# PAPAYA_PCB.net
KiCad netlist of a schematic drawn in Altium Designer
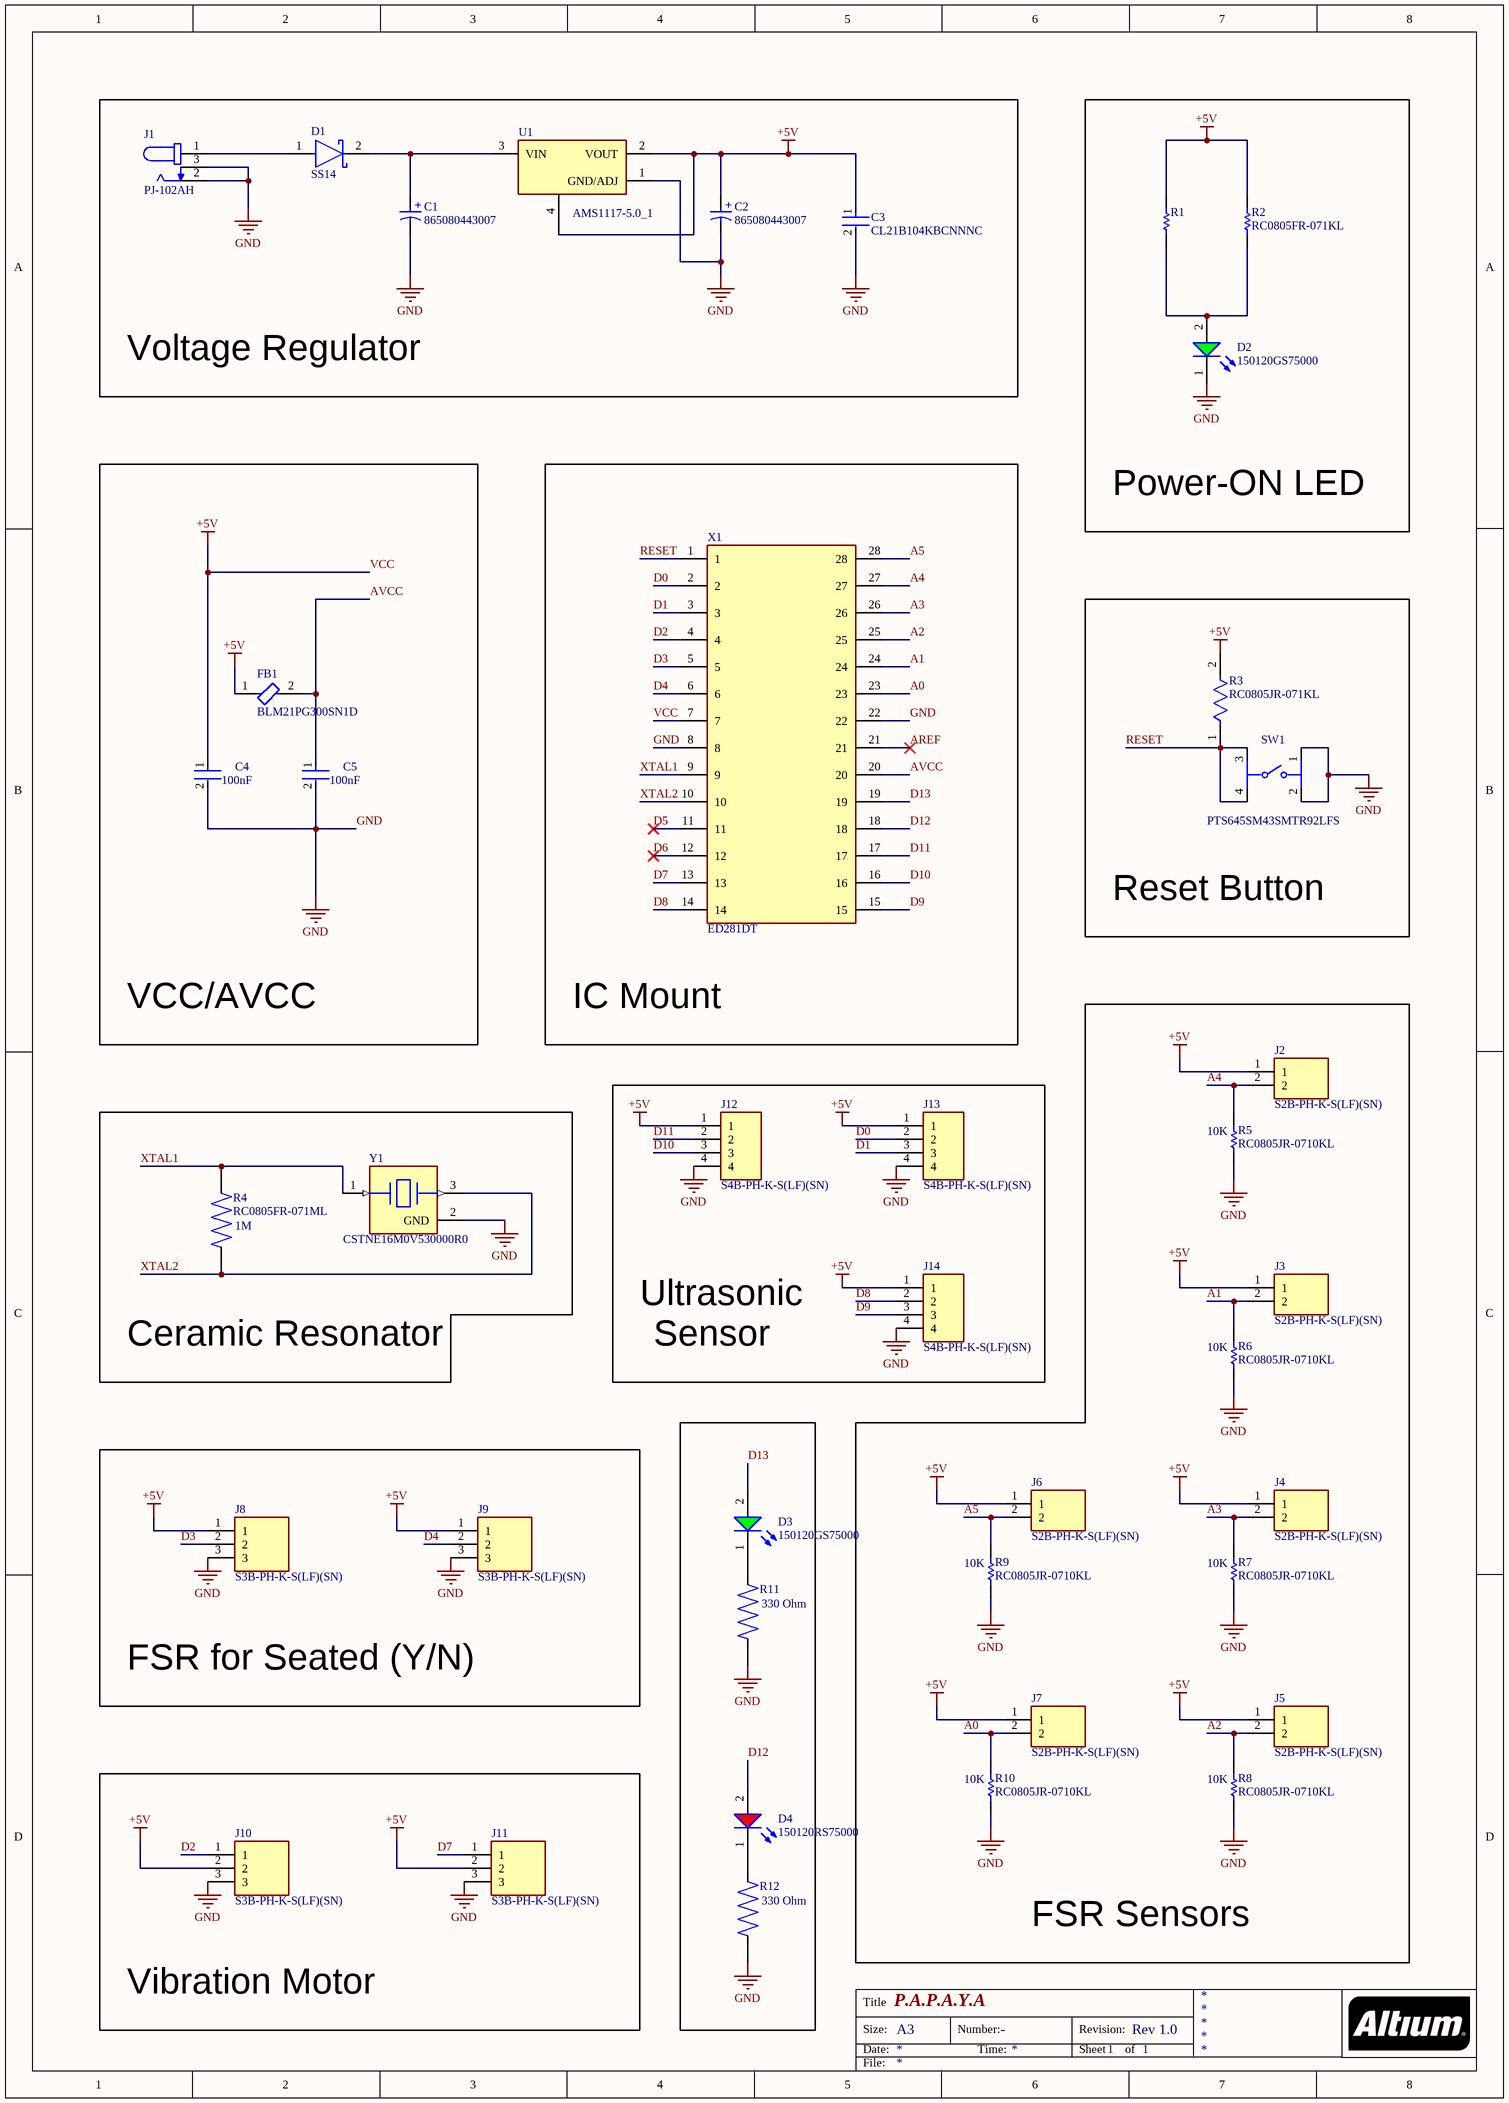
[diagram p0: PAPAYA_PCB.SchDoc]

(export (version "E")
  (design (tool "Eeschema 10.0.6"))
  (components
    (comp (ref "C1")
      (value "865080443007")
      (footprint "WCAP-ASLI_D6.3H5.5")
      (description "865080443007 WCAP-ASLI Aluminum Electrolytic Capacitors")
      (fields (field (name "TOLERANCE") "20%"))
      (libsource (lib "Altium Content Vault") (part "Capacitor_Polarized"))
    )
    (comp (ref "C2")
      (value "865080443007")
      (footprint "WCAP-ASLI_D6.3H5.5")
      (description "865080443007 WCAP-ASLI Aluminum Electrolytic Capacitors")
      (fields (field (name "TOLERANCE") "20%"))
      (libsource (lib "Altium Content Vault") (part "Capacitor_Polarized"))
    )
    (comp (ref "C3")
      (value "CL21B104KBCNNNC")
      (footprint "FP-CL21-IPC_C")
      (description "CL21 Series 0805 100nF 50V ±10% Tolerance X7R Multilayer Ceramic Chip Capacitor")
      (fields (field (name "TOLERANCE") "10%") (field (name "VOLTAGE") "50V"))
      (libsource (lib "Altium Content Vault") (part "b4654b650e69147ec39a6b967a45e02"))
    )
    (comp (ref "C4")
      (value "CL21B104KBCNNNC")
      (footprint "FP-CL21-IPC_C")
      (description "CL21 Series 0805 100nF 50V ±10% Tolerance X7R Multilayer Ceramic Chip Capacitor")
      (fields
        (field (name "TOLERANCE") "10%")
        (field (name "CAPACITANCE") "100nF")
        (field (name "VOLTAGE") "50V")
      )
      (libsource (lib "Altium Content Vault") (part "b4654b650e69147ec39a6b967a45e02"))
    )
    (comp (ref "C5")
      (value "CL21B104KBCNNNC")
      (footprint "FP-CL21-IPC_C")
      (description "CL21 Series 0805 100nF 50V ±10% Tolerance X7R Multilayer Ceramic Chip Capacitor")
      (fields
        (field (name "TOLERANCE") "10%")
        (field (name "CAPACITANCE") "100nF")
        (field (name "VOLTAGE") "50V")
      )
      (libsource (lib "Altium Content Vault") (part "b4654b650e69147ec39a6b967a45e02"))
    )
    (comp (ref "D1")
      (value "SS14")
      (footprint "FP-403AE-MFG")
      (description "DIODE SCHOTTKY 40V 1A SMA")
      (fields
        (field (name "MANUFACTURER") "ON Semiconductor")
        (field (name "OCTOPART") "https://octopart.com/ss14-on+semiconductor-29205033")
      )
      (libsource (lib "Altium Content Vault") (part "360ad2f4ac25a952324d13796385471"))
    )
    (comp (ref "D2")
      (value "150120GS75000")
      (footprint "WL-SMCW_1206_150120xx75000")
      (description "WURTH ELEKTRONIK - 150080GS75000 - LED, Green, SMD, 0805, 30 mA, 3.2 V, 520 nm")
      (libsource (lib "Altium Content Vault") (part "LED_Green_2A-1K"))
    )
    (comp (ref "D3")
      (value "150120GS75000")
      (footprint "WL-SMCW_1206_150120xx75000")
      (description "WURTH ELEKTRONIK - 150080GS75000 - LED, Green, SMD, 0805, 30 mA, 3.2 V, 520 nm")
      (libsource (lib "Altium Content Vault") (part "LED_Green_2A-1K"))
    )
    (comp (ref "D4")
      (value "150120RS75000")
      (footprint "WL-SMCW_1206_150120xx75000")
      (description "LED Uni-Color Red 630nm 2-Pin Chip 0805(2012Metric) T/R")
      (libsource (lib "Altium Content Vault") (part "LED_Red_2A-1K"))
    )
    (comp (ref "FB1")
      (value "BLM21PG300SN1D")
      (footprint "FP-BLM21-0_2-t0_85-e0_5-d-MFG")
      (description "Chip Ferrite Bead, 0805, 30Ω @ 100MHz, 0.014Ω, , 4A")
      (fields (field (name "TOLERANCE") "25%"))
      (libsource (lib "Altium Content Vault") (part "5f30dd21d616792df468990f7003faa"))
    )
    (comp (ref "J1")
      (value "PJ-102AH")
      (footprint "CUI_PJ-102AH")
      (description "2.0 x 6.5 mm, 5.0 A, Horizontal, Through Hole, Tapered Pins, Dc Power Jack Connector")
      (fields (field (name "MF") "Same Sky"))
      (libsource (lib "Schlib1") (part "PJ-102AH"))
    )
    (comp (ref "J2")
      (value "S2B-PH-K-S(LF)(SN)")
      (footprint "JST_S2B-PH-K-S(LF)(SN)")
      (description "Connector Header Through Hole, Right Angle 2 position")
      (fields (field (name "MF") "JST Sales America Inc."))
      (libsource (lib "Schlib1") (part "S2B-PH-K-S(LF)(SN)"))
    )
    (comp (ref "J3")
      (value "S2B-PH-K-S(LF)(SN)")
      (footprint "JST_S2B-PH-K-S(LF)(SN)")
      (description "Connector Header Through Hole, Right Angle 2 position")
      (fields (field (name "MF") "JST Sales America Inc."))
      (libsource (lib "Schlib1") (part "S2B-PH-K-S(LF)(SN)"))
    )
    (comp (ref "J4")
      (value "S2B-PH-K-S(LF)(SN)")
      (footprint "JST_S2B-PH-K-S(LF)(SN)")
      (description "Connector Header Through Hole, Right Angle 2 position")
      (fields (field (name "MF") "JST Sales America Inc."))
      (libsource (lib "Schlib1") (part "S2B-PH-K-S(LF)(SN)"))
    )
    (comp (ref "J5")
      (value "S2B-PH-K-S(LF)(SN)")
      (footprint "JST_S2B-PH-K-S(LF)(SN)")
      (description "Connector Header Through Hole, Right Angle 2 position")
      (fields (field (name "MF") "JST Sales America Inc."))
      (libsource (lib "Schlib1") (part "S2B-PH-K-S(LF)(SN)"))
    )
    (comp (ref "J6")
      (value "S2B-PH-K-S(LF)(SN)")
      (footprint "JST_S2B-PH-K-S(LF)(SN)")
      (description "Connector Header Through Hole, Right Angle 2 position")
      (fields (field (name "MF") "JST Sales America Inc."))
      (libsource (lib "Schlib1") (part "S2B-PH-K-S(LF)(SN)"))
    )
    (comp (ref "J7")
      (value "S2B-PH-K-S(LF)(SN)")
      (footprint "JST_S2B-PH-K-S(LF)(SN)")
      (description "Connector Header Through Hole, Right Angle 2 position")
      (fields (field (name "MF") "JST Sales America Inc."))
      (libsource (lib "Schlib1") (part "S2B-PH-K-S(LF)(SN)"))
    )
    (comp (ref "J8")
      (value "S3B-PH-K-S(LF)(SN)")
      (footprint "JST_S3B-PH-K-S(LF)(SN)")
      (description "Connector Header Through Hole, Right Angle 3 position 0.079\" (2.00mm)")
      (libsource (lib "Schlib1") (part "S3B-PH-K-S(LF)(SN)"))
    )
    (comp (ref "J9")
      (value "S3B-PH-K-S(LF)(SN)")
      (footprint "JST_S3B-PH-K-S(LF)(SN)")
      (description "Connector Header Through Hole, Right Angle 3 position 0.079\" (2.00mm)")
      (libsource (lib "Schlib1") (part "S3B-PH-K-S(LF)(SN)"))
    )
    (comp (ref "J10")
      (value "S3B-PH-K-S(LF)(SN)")
      (footprint "JST_S3B-PH-K-S(LF)(SN)")
      (description "Connector Header Through Hole, Right Angle 3 position 0.079\" (2.00mm)")
      (libsource (lib "Schlib1") (part "S3B-PH-K-S(LF)(SN)"))
    )
    (comp (ref "J11")
      (value "S3B-PH-K-S(LF)(SN)")
      (footprint "JST_S3B-PH-K-S(LF)(SN)")
      (description "Connector Header Through Hole, Right Angle 3 position 0.079\" (2.00mm)")
      (libsource (lib "Schlib1") (part "S3B-PH-K-S(LF)(SN)"))
    )
    (comp (ref "J12")
      (value "S4B-PH-K-S(LF)(SN)")
      (footprint "JST_S4B-PH-K-S(LF)(SN)")
      (description "Connector Header Through Hole, Right Angle 4 position 0.079 _2.00mm_")
      (fields (field (name "MP") "S4B-PH-K-S_LF__SN_") (field (name "MF") "JST Sales"))
      (libsource (lib "Schlib1") (part "S4B-PH-K-S(LF)(SN)"))
    )
    (comp (ref "J13")
      (value "S4B-PH-K-S(LF)(SN)")
      (footprint "JST_S4B-PH-K-S(LF)(SN)")
      (description "Connector Header Through Hole, Right Angle 4 position 0.079 _2.00mm_")
      (fields (field (name "MP") "S4B-PH-K-S_LF__SN_") (field (name "MF") "JST Sales"))
      (libsource (lib "Schlib1") (part "S4B-PH-K-S(LF)(SN)"))
    )
    (comp (ref "J14")
      (value "S4B-PH-K-S(LF)(SN)")
      (footprint "JST_S4B-PH-K-S(LF)(SN)")
      (description "Connector Header Through Hole, Right Angle 4 position 0.079 _2.00mm_")
      (fields (field (name "MP") "S4B-PH-K-S_LF__SN_") (field (name "MF") "JST Sales"))
      (libsource (lib "Schlib1") (part "S4B-PH-K-S(LF)(SN)"))
    )
    (comp (ref "R1")
      (value "RC0805FR-071KL")
      (footprint "RESC2013X60X35ML10T20")
      (description "Chip Resistor, 1 KOhm, +/- 1%, 125 mW, -55 to 155 degC, 0805 (2012 Metric), RoHS, Tape and Reel")
      (fields (field (name "TOLERANCE") "1%") (field (name "MANUFACTURER") "Yageo"))
      (libsource (lib "Altium Content Vault") (part "RES-2"))
    )
    (comp (ref "R2")
      (value "RC0805FR-071KL")
      (footprint "RESC2013X60X35ML10T20")
      (description "Chip Resistor, 1 KOhm, +/- 1%, 125 mW, -55 to 155 degC, 0805 (2012 Metric), RoHS, Tape and Reel")
      (fields (field (name "TOLERANCE") "1%") (field (name "MANUFACTURER") "Yageo"))
      (libsource (lib "Altium Content Vault") (part "RES-2"))
    )
    (comp (ref "R3")
      (value "RC0805JR-071KL")
      (footprint "FP-RC0805-0_6-MFG")
      (description "RES SMD 1K OHM 5% 1/8W 0805")
      (fields (field (name "TOLERANCE") "5%"))
      (libsource (lib "Altium Content Vault") (part "1029c3af85768c4190bb7ad29bc67b5"))
    )
    (comp (ref "R4")
      (value "RC0805FR-071ML")
      (footprint "RESC2012X60N")
      (description "1 MOhms Â±1% 0.125W, 1/8W Chip Resistor 0805 (2012 Metric) Moisture Resistant Thick Film")
      (fields (field (name "ALTIUM_VALUE") "1M") (field (name "MF") "Yageo"))
      (libsource (lib "Schlib1") (part "RC0805FR-071ML"))
    )
    (comp (ref "R5")
      (value "RC0805JR-0710KL")
      (footprint "RESC2013X60X35ML10T20")
      (description "Chip Resistor, 10 KOhm, +/- 5%, 0.125 W, -55 to 155 degC, 0805 (2012 Metric), RoHS, Tape and Reel")
      (fields (field (name "MANUFACTURER") "Yageo") (field (name "RESISTANCE") "10K"))
      (libsource (lib "Altium Content Vault") (part "RES-2"))
    )
    (comp (ref "R6")
      (value "RC0805JR-0710KL")
      (footprint "RESC2013X60X35ML10T20")
      (description "Chip Resistor, 10 KOhm, +/- 5%, 0.125 W, -55 to 155 degC, 0805 (2012 Metric), RoHS, Tape and Reel")
      (fields (field (name "MANUFACTURER") "Yageo") (field (name "RESISTANCE") "10K"))
      (libsource (lib "Altium Content Vault") (part "RES-2"))
    )
    (comp (ref "R7")
      (value "RC0805JR-0710KL")
      (footprint "RESC2013X60X35ML10T20")
      (description "Chip Resistor, 10 KOhm, +/- 5%, 0.125 W, -55 to 155 degC, 0805 (2012 Metric), RoHS, Tape and Reel")
      (fields (field (name "MANUFACTURER") "Yageo") (field (name "RESISTANCE") "10K"))
      (libsource (lib "Altium Content Vault") (part "RES-2"))
    )
    (comp (ref "R8")
      (value "RC0805JR-0710KL")
      (footprint "RESC2013X60X35ML10T20")
      (description "Chip Resistor, 10 KOhm, +/- 5%, 0.125 W, -55 to 155 degC, 0805 (2012 Metric), RoHS, Tape and Reel")
      (fields (field (name "MANUFACTURER") "Yageo") (field (name "RESISTANCE") "10K"))
      (libsource (lib "Altium Content Vault") (part "RES-2"))
    )
    (comp (ref "R9")
      (value "RC0805JR-0710KL")
      (footprint "RESC2013X60X35ML10T20")
      (description "Chip Resistor, 10 KOhm, +/- 5%, 0.125 W, -55 to 155 degC, 0805 (2012 Metric), RoHS, Tape and Reel")
      (fields (field (name "MANUFACTURER") "Yageo") (field (name "RESISTANCE") "10K"))
      (libsource (lib "Altium Content Vault") (part "RES-2"))
    )
    (comp (ref "R10")
      (value "RC0805JR-0710KL")
      (footprint "RESC2013X60X35ML10T20")
      (description "Chip Resistor, 10 KOhm, +/- 5%, 0.125 W, -55 to 155 degC, 0805 (2012 Metric), RoHS, Tape and Reel")
      (fields (field (name "MANUFACTURER") "Yageo") (field (name "RESISTANCE") "10K"))
      (libsource (lib "Altium Content Vault") (part "RES-2"))
    )
    (comp (ref "R11")
      (value "330 Ohm")
      (footprint "RESC2012X60N")
      (fields
        (field (name "MP") "RC0805JR-07330RL")
        (field (name "MF") "Yageo")
        (field (name "DIGI-KEY_PART_NUMBER") "311-330ARCT-ND")
      )
      (libsource (lib "Schlib1") (part "RC0805JR-07330RL"))
    )
    (comp (ref "R12")
      (value "330 Ohm")
      (footprint "RESC2012X60N")
      (fields
        (field (name "MP") "RC0805JR-07330RL")
        (field (name "MF") "Yageo")
        (field (name "DIGI-KEY_PART_NUMBER") "311-330ARCT-ND")
      )
      (libsource (lib "Schlib1") (part "RC0805JR-07330RL"))
    )
    (comp (ref "SW1")
      (value "PTS645SM43SMTR92LFS")
      (footprint "SWITCH_43SMTR92LFS")
      (description "SWITCH TACTILE SPST-NO 0.05A 12V")
      (libsource (lib "Schlib1") (part "PTS645SM43SMTR92LFS_1"))
    )
    (comp (ref "U1")
      (value "AMS1117-5.0_1")
      (footprint "SOT229P700X180-4N")
      (description "1A LOW DROPOUT VOLTAGE REGULATOR")
      (fields (field (name "MP") "AMS1117-5.0") (field (name "MF") "ams"))
      (libsource (lib "Schlib1") (part "AMS1117-5.0_1"))
    )
    (comp (ref "X1")
      (value "ED281DT")
      (footprint "OST_ED281DT")
      (description "CONN IC DIP SOCKET 28POS TIN")
      (fields (field (name "MP") "altium_native_batch"))
      (libsource (lib "Schlib1") (part "ED281DT"))
    )
    (comp (ref "Y1")
      (value "CSTNE16M0V530000R0")
      (footprint "FP-CSTNE16M0V530000R0-MFG")
      (description "CERAMIC RES 16.0000MHZ 15PF SMD")
      (fields (field (name "TOLERANCE") "0.5%") (field (name "MANUFACTURER") "Murata"))
      (libsource (lib "Altium Content Vault") (part "f88508b02107a2c8e6f46217c19d2b8"))
    )
  )
  (nets
    (net (code "1") (name "+5V") (class "Default")
      (node (ref "C2") (pin "1") (pinfunction "P_1") (pintype "passive"))
      (node (ref "C3") (pin "1") (pinfunction "1_1") (pintype "passive"))
      (node (ref "C4") (pin "1") (pinfunction "1_1") (pintype "passive"))
      (node (ref "FB1") (pin "1") (pinfunction "1_1") (pintype "passive"))
      (node (ref "J10") (pin "2") (pinfunction "2_2") (pintype "passive"))
      (node (ref "J11") (pin "2") (pinfunction "2_2") (pintype "passive"))
      (node (ref "J12") (pin "1") (pinfunction "1_1") (pintype "passive"))
      (node (ref "J13") (pin "1") (pinfunction "1_1") (pintype "passive"))
      (node (ref "J14") (pin "1") (pinfunction "1_1") (pintype "passive"))
      (node (ref "J2") (pin "1") (pinfunction "1_1") (pintype "passive"))
      (node (ref "J3") (pin "1") (pinfunction "1_1") (pintype "passive"))
      (node (ref "J4") (pin "1") (pinfunction "1_1") (pintype "passive"))
      (node (ref "J5") (pin "1") (pinfunction "1_1") (pintype "passive"))
      (node (ref "J6") (pin "1") (pinfunction "1_1") (pintype "passive"))
      (node (ref "J7") (pin "1") (pinfunction "1_1") (pintype "passive"))
      (node (ref "J8") (pin "1") (pinfunction "1_1") (pintype "passive"))
      (node (ref "J9") (pin "1") (pinfunction "1_1") (pintype "passive"))
      (node (ref "R1") (pin "2") (pinfunction "2_2") (pintype "passive"))
      (node (ref "R2") (pin "2") (pinfunction "2_2") (pintype "passive"))
      (node (ref "R3") (pin "2") (pinfunction "2_2") (pintype "passive"))
      (node (ref "U1") (pin "2") (pinfunction "VOUT_2") (pintype "power_in"))
      (node (ref "U1") (pin "4") (pinfunction "TAB_4") (pintype "passive"))
      (node (ref "X1") (pin "7") (pinfunction "7_7") (pintype "passive"))
    )
    (net (code "2") (name "/A0") (class "Default")
      (node (ref "J7") (pin "2") (pinfunction "2_2") (pintype "passive"))
      (node (ref "R10") (pin "2") (pinfunction "2_2") (pintype "passive"))
      (node (ref "X1") (pin "23") (pinfunction "23_23") (pintype "passive"))
    )
    (net (code "3") (name "/A1") (class "Default")
      (node (ref "J3") (pin "2") (pinfunction "2_2") (pintype "passive"))
      (node (ref "R6") (pin "2") (pinfunction "2_2") (pintype "passive"))
      (node (ref "X1") (pin "24") (pinfunction "24_24") (pintype "passive"))
    )
    (net (code "4") (name "/A2") (class "Default")
      (node (ref "J5") (pin "2") (pinfunction "2_2") (pintype "passive"))
      (node (ref "R8") (pin "2") (pinfunction "2_2") (pintype "passive"))
      (node (ref "X1") (pin "25") (pinfunction "25_25") (pintype "passive"))
    )
    (net (code "5") (name "/A3") (class "Default")
      (node (ref "J4") (pin "2") (pinfunction "2_2") (pintype "passive"))
      (node (ref "R7") (pin "2") (pinfunction "2_2") (pintype "passive"))
      (node (ref "X1") (pin "26") (pinfunction "26_26") (pintype "passive"))
    )
    (net (code "6") (name "/A4") (class "Default")
      (node (ref "J2") (pin "2") (pinfunction "2_2") (pintype "passive"))
      (node (ref "R5") (pin "2") (pinfunction "2_2") (pintype "passive"))
      (node (ref "X1") (pin "27") (pinfunction "27_27") (pintype "passive"))
    )
    (net (code "7") (name "/A5") (class "Default")
      (node (ref "J6") (pin "2") (pinfunction "2_2") (pintype "passive"))
      (node (ref "R9") (pin "2") (pinfunction "2_2") (pintype "passive"))
      (node (ref "X1") (pin "28") (pinfunction "28_28") (pintype "passive"))
    )
    (net (code "8") (name "/AREF") (class "Default")
      (node (ref "X1") (pin "21") (pinfunction "21_21") (pintype "passive+no_connect"))
    )
    (net (code "9") (name "/AVCC") (class "Default")
      (node (ref "C5") (pin "1") (pinfunction "1_1") (pintype "passive"))
      (node (ref "FB1") (pin "2") (pinfunction "2_2") (pintype "passive"))
      (node (ref "X1") (pin "20") (pinfunction "20_20") (pintype "passive"))
    )
    (net (code "10") (name "/D0") (class "Default")
      (node (ref "J13") (pin "2") (pinfunction "2_2") (pintype "passive"))
      (node (ref "X1") (pin "2") (pinfunction "2_2") (pintype "passive"))
    )
    (net (code "11") (name "/D1") (class "Default")
      (node (ref "J13") (pin "3") (pinfunction "3_3") (pintype "passive"))
      (node (ref "X1") (pin "3") (pinfunction "3_3") (pintype "passive"))
    )
    (net (code "12") (name "/D2") (class "Default")
      (node (ref "J10") (pin "1") (pinfunction "1_1") (pintype "passive"))
      (node (ref "X1") (pin "4") (pinfunction "4_4") (pintype "passive"))
    )
    (net (code "13") (name "/D3") (class "Default")
      (node (ref "J8") (pin "2") (pinfunction "2_2") (pintype "passive"))
      (node (ref "X1") (pin "5") (pinfunction "5_5") (pintype "passive"))
    )
    (net (code "14") (name "/D4") (class "Default")
      (node (ref "J9") (pin "2") (pinfunction "2_2") (pintype "passive"))
      (node (ref "X1") (pin "6") (pinfunction "6_6") (pintype "passive"))
    )
    (net (code "15") (name "/D5") (class "Default")
      (node (ref "X1") (pin "11") (pinfunction "11_11") (pintype "passive+no_connect"))
    )
    (net (code "16") (name "/D6") (class "Default")
      (node (ref "X1") (pin "12") (pinfunction "12_12") (pintype "passive+no_connect"))
    )
    (net (code "17") (name "/D7") (class "Default")
      (node (ref "J11") (pin "1") (pinfunction "1_1") (pintype "passive"))
      (node (ref "X1") (pin "13") (pinfunction "13_13") (pintype "passive"))
    )
    (net (code "18") (name "/D8") (class "Default")
      (node (ref "J14") (pin "2") (pinfunction "2_2") (pintype "passive"))
      (node (ref "X1") (pin "14") (pinfunction "14_14") (pintype "passive"))
    )
    (net (code "19") (name "/D9") (class "Default")
      (node (ref "J14") (pin "3") (pinfunction "3_3") (pintype "passive"))
      (node (ref "X1") (pin "15") (pinfunction "15_15") (pintype "passive"))
    )
    (net (code "20") (name "/D10") (class "Default")
      (node (ref "J12") (pin "3") (pinfunction "3_3") (pintype "passive"))
      (node (ref "X1") (pin "16") (pinfunction "16_16") (pintype "passive"))
    )
    (net (code "21") (name "/D11") (class "Default")
      (node (ref "J12") (pin "2") (pinfunction "2_2") (pintype "passive"))
      (node (ref "X1") (pin "17") (pinfunction "17_17") (pintype "passive"))
    )
    (net (code "22") (name "/D12") (class "Default")
      (node (ref "D4") (pin "2") (pinfunction "A_2") (pintype "passive"))
      (node (ref "X1") (pin "18") (pinfunction "18_18") (pintype "passive"))
    )
    (net (code "23") (name "/D13") (class "Default")
      (node (ref "D3") (pin "2") (pinfunction "A_2") (pintype "passive"))
      (node (ref "X1") (pin "19") (pinfunction "19_19") (pintype "passive"))
    )
    (net (code "24") (name "/RESET") (class "Default")
      (node (ref "R3") (pin "1") (pinfunction "1_1") (pintype "passive"))
      (node (ref "SW1") (pin "3") (pinfunction "3_3") (pintype "passive"))
      (node (ref "SW1") (pin "4") (pinfunction "4_4") (pintype "passive"))
      (node (ref "X1") (pin "1") (pinfunction "1_1") (pintype "passive"))
    )
    (net (code "25") (name "/XTAL1") (class "Default")
      (node (ref "R4") (pin "2") (pinfunction "2_2") (pintype "passive"))
      (node (ref "X1") (pin "9") (pinfunction "9_9") (pintype "passive"))
      (node (ref "Y1") (pin "1") (pinfunction "Input_1") (pintype "input"))
    )
    (net (code "26") (name "/XTAL2") (class "Default")
      (node (ref "R4") (pin "1") (pinfunction "1_1") (pintype "passive"))
      (node (ref "X1") (pin "10") (pinfunction "10_10") (pintype "passive"))
      (node (ref "Y1") (pin "3") (pinfunction "Output_3") (pintype "output"))
    )
    (net (code "27") (name "GND") (class "Default")
      (node (ref "C1") (pin "2") (pinfunction "N_2") (pintype "passive"))
      (node (ref "C2") (pin "2") (pinfunction "N_2") (pintype "passive"))
      (node (ref "C3") (pin "2") (pinfunction "2_2") (pintype "passive"))
      (node (ref "C4") (pin "2") (pinfunction "2_2") (pintype "passive"))
      (node (ref "C5") (pin "2") (pinfunction "2_2") (pintype "passive"))
      (node (ref "D2") (pin "1") (pinfunction "K_1") (pintype "passive"))
      (node (ref "J1") (pin "2") (pinfunction "2_2") (pintype "passive"))
      (node (ref "J1") (pin "3") (pinfunction "3_3") (pintype "passive"))
      (node (ref "J10") (pin "3") (pinfunction "3_3") (pintype "passive"))
      (node (ref "J11") (pin "3") (pinfunction "3_3") (pintype "passive"))
      (node (ref "J12") (pin "4") (pinfunction "4_4") (pintype "passive"))
      (node (ref "J13") (pin "4") (pinfunction "4_4") (pintype "passive"))
      (node (ref "J14") (pin "4") (pinfunction "4_4") (pintype "passive"))
      (node (ref "J8") (pin "3") (pinfunction "3_3") (pintype "passive"))
      (node (ref "J9") (pin "3") (pinfunction "3_3") (pintype "passive"))
      (node (ref "R10") (pin "1") (pinfunction "1_1") (pintype "passive"))
      (node (ref "R11") (pin "1") (pinfunction "1_1") (pintype "passive"))
      (node (ref "R12") (pin "1") (pinfunction "1_1") (pintype "passive"))
      (node (ref "R5") (pin "1") (pinfunction "1_1") (pintype "passive"))
      (node (ref "R6") (pin "1") (pinfunction "1_1") (pintype "passive"))
      (node (ref "R7") (pin "1") (pinfunction "1_1") (pintype "passive"))
      (node (ref "R8") (pin "1") (pinfunction "1_1") (pintype "passive"))
      (node (ref "R9") (pin "1") (pinfunction "1_1") (pintype "passive"))
      (node (ref "SW1") (pin "1") (pinfunction "1_1") (pintype "passive"))
      (node (ref "SW1") (pin "2") (pinfunction "2_2") (pintype "passive"))
      (node (ref "U1") (pin "1") (pinfunction "GND/ADJ_1") (pintype "power_in"))
      (node (ref "X1") (pin "22") (pinfunction "22_22") (pintype "passive"))
      (node (ref "X1") (pin "8") (pinfunction "8_8") (pintype "passive"))
      (node (ref "Y1") (pin "2") (pinfunction "GND_2") (pintype "power_in"))
    )
    (net (code "28") (name "Net-(C1-P)") (class "Default")
      (node (ref "C1") (pin "1") (pinfunction "P_1") (pintype "passive"))
      (node (ref "D1") (pin "2") (pinfunction "C_2") (pintype "passive"))
      (node (ref "U1") (pin "3") (pinfunction "VIN_3") (pintype "power_in"))
    )
    (net (code "29") (name "Net-(D1-A)") (class "Default")
      (node (ref "D1") (pin "1") (pinfunction "A_1") (pintype "passive"))
      (node (ref "J1") (pin "1") (pinfunction "1_1") (pintype "passive"))
    )
    (net (code "30") (name "Net-(D2-A)") (class "Default")
      (node (ref "D2") (pin "2") (pinfunction "A_2") (pintype "passive"))
      (node (ref "R1") (pin "1") (pinfunction "1_1") (pintype "passive"))
      (node (ref "R2") (pin "1") (pinfunction "1_1") (pintype "passive"))
    )
    (net (code "31") (name "Net-(D3-K)") (class "Default")
      (node (ref "D3") (pin "1") (pinfunction "K_1") (pintype "passive"))
      (node (ref "R11") (pin "2") (pinfunction "2_2") (pintype "passive"))
    )
    (net (code "32") (name "Net-(D4-K)") (class "Default")
      (node (ref "D4") (pin "1") (pinfunction "K_1") (pintype "passive"))
      (node (ref "R12") (pin "2") (pinfunction "2_2") (pintype "passive"))
    )
  )
)
